# Sheet1.net
KiCad netlist of a schematic drawn in Altium Designer
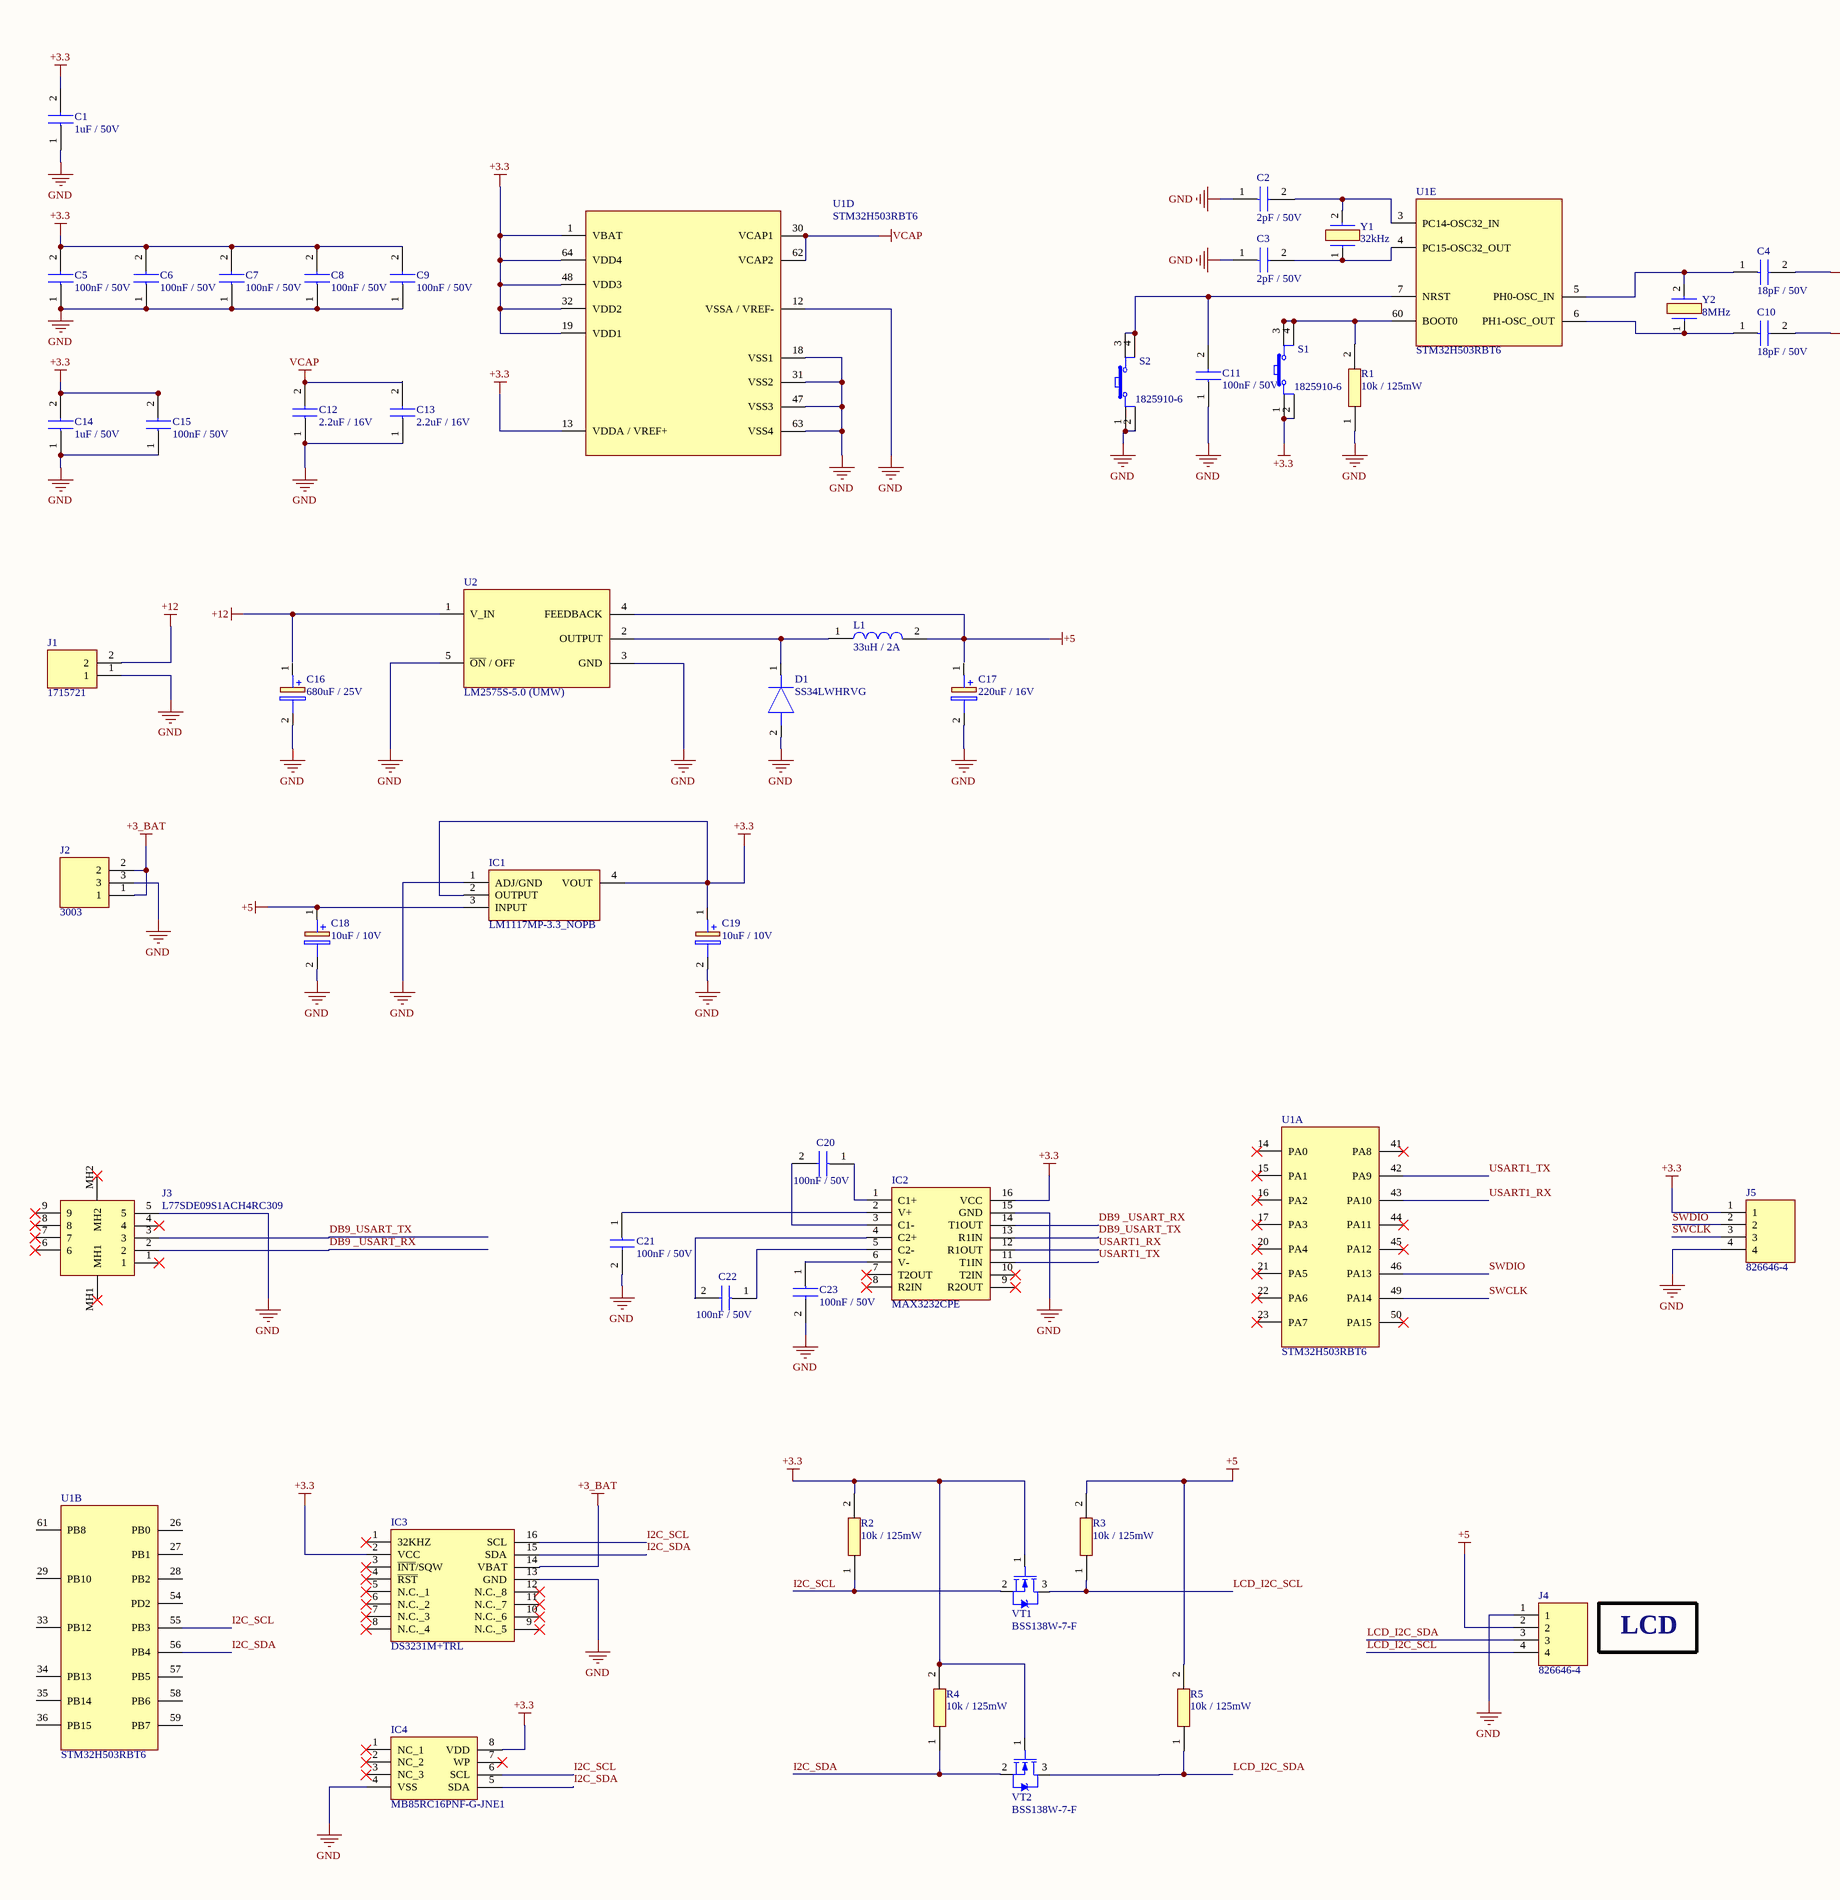
[diagram p0: Sheet1.SchDoc, left]
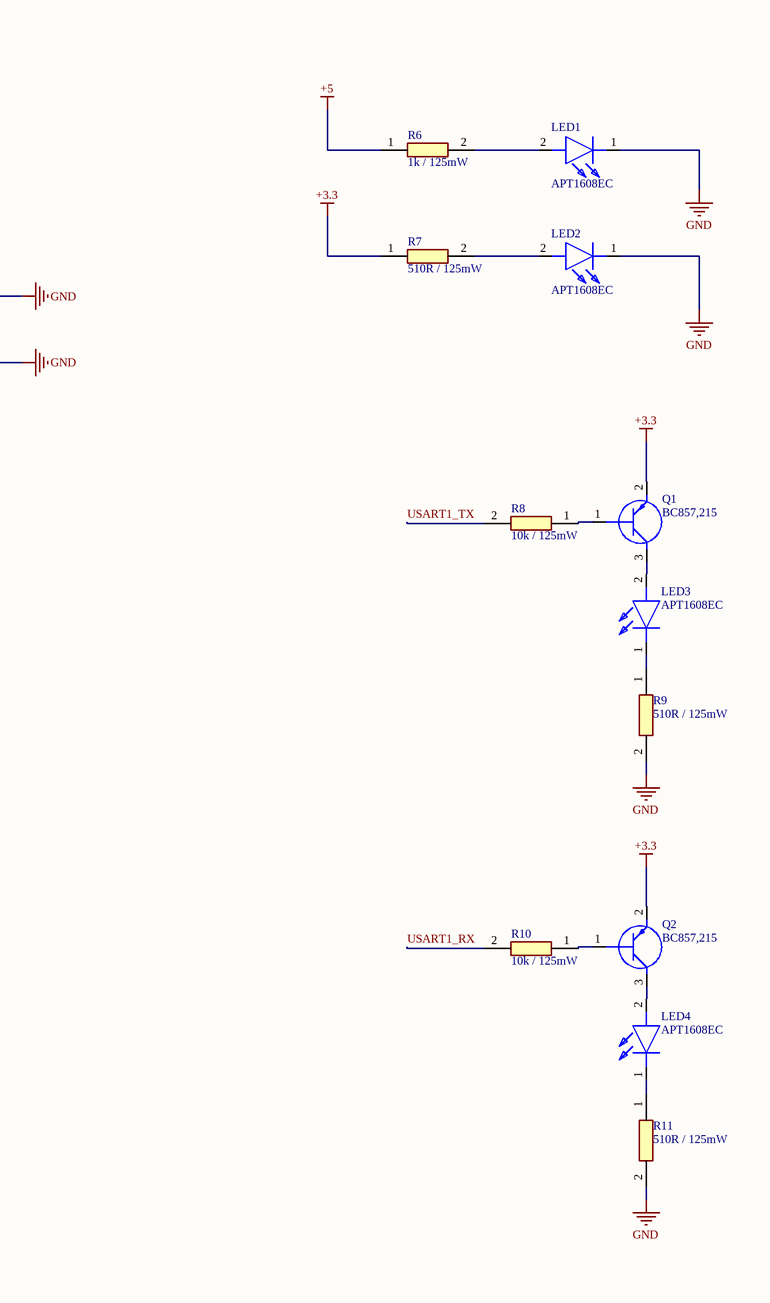
[diagram p1: Sheet1.SchDoc, right]

(export (version "E")
  (design (tool "Eeschema 10.0.6"))
  (components
    (comp (ref "C1")
      (value "1uF / 50V")
      (footprint "SamacSys:CAPC2012X145N")
      (description "Capacitor")
      (fields
        (field (name "MANUFACTURER_PART_NUMBER") "GRM21BR71H105KA12L")
        (field (name "MOUSER PART NUMBER") "81-GRM21BR71H105KA2L")
      )
      (libsource (lib "*") (part "GRM21BR71H105KA12L"))
    )
    (comp (ref "C2")
      (value "2pF / 50V")
      (footprint "SamacSys:C0805")
      (description "Capacitor")
      (fields (field (name "MANUFACTURER_PART_NUMBER") "C0805C209C5GACTU"))
      (libsource (lib "*") (part "C0805C209C5GACTU"))
    )
    (comp (ref "C3")
      (value "2pF / 50V")
      (footprint "SamacSys:C0805")
      (description "Capacitor")
      (fields (field (name "MANUFACTURER_PART_NUMBER") "C0805C209C5GACTU"))
      (libsource (lib "*") (part "C0805C209C5GACTU"))
    )
    (comp (ref "C4")
      (value "18pF / 50V")
      (footprint "SamacSys:C0805")
      (description "Capacitor")
      (fields
        (field (name "MANUFACTURER_PART_NUMBER") "C0805C180G5GACTU")
        (field (name "MOUSER PART NUMBER") "80-C0805C180G5G")
      )
      (libsource (lib "*") (part "C0805C180G5GACTU"))
    )
    (comp (ref "C5")
      (value "100nF / 50V")
      (footprint "SamacSys:CAPC2012X95N")
      (description "Capacitor")
      (fields
        (field (name "MANUFACTURER_PART_NUMBER") "CL21B104KBCNNNC")
        (field (name "MOUSER PART NUMBER") "187-CL21B104KBCNNNC")
      )
      (libsource (lib "*") (part "CL21B104KBCNNNC"))
    )
    (comp (ref "C6")
      (value "100nF / 50V")
      (footprint "SamacSys:CAPC2012X95N")
      (description "Capacitor")
      (fields
        (field (name "MANUFACTURER_PART_NUMBER") "CL21B104KBCNNNC")
        (field (name "MOUSER PART NUMBER") "187-CL21B104KBCNNNC")
      )
      (libsource (lib "*") (part "CL21B104KBCNNNC"))
    )
    (comp (ref "C7")
      (value "100nF / 50V")
      (footprint "SamacSys:CAPC2012X95N")
      (description "Capacitor")
      (fields
        (field (name "MANUFACTURER_PART_NUMBER") "CL21B104KBCNNNC")
        (field (name "MOUSER PART NUMBER") "187-CL21B104KBCNNNC")
      )
      (libsource (lib "*") (part "CL21B104KBCNNNC"))
    )
    (comp (ref "C8")
      (value "100nF / 50V")
      (footprint "SamacSys:CAPC2012X95N")
      (description "Capacitor")
      (fields
        (field (name "MANUFACTURER_PART_NUMBER") "CL21B104KBCNNNC")
        (field (name "MOUSER PART NUMBER") "187-CL21B104KBCNNNC")
      )
      (libsource (lib "*") (part "CL21B104KBCNNNC"))
    )
    (comp (ref "C9")
      (value "100nF / 50V")
      (footprint "SamacSys:CAPC2012X95N")
      (description "Capacitor")
      (fields
        (field (name "MANUFACTURER_PART_NUMBER") "CL21B104KBCNNNC")
        (field (name "MOUSER PART NUMBER") "187-CL21B104KBCNNNC")
      )
      (libsource (lib "*") (part "CL21B104KBCNNNC"))
    )
    (comp (ref "C10")
      (value "18pF / 50V")
      (footprint "SamacSys:C0805")
      (description "Capacitor")
      (fields
        (field (name "MANUFACTURER_PART_NUMBER") "C0805C180G5GACTU")
        (field (name "MOUSER PART NUMBER") "80-C0805C180G5G")
      )
      (libsource (lib "*") (part "C0805C180G5GACTU"))
    )
    (comp (ref "C11")
      (value "100nF / 50V")
      (footprint "SamacSys:CAPC2012X95N")
      (description "Capacitor")
      (fields
        (field (name "MANUFACTURER_PART_NUMBER") "CL21B104KBCNNNC")
        (field (name "MOUSER PART NUMBER") "187-CL21B104KBCNNNC")
      )
      (libsource (lib "*") (part "CL21B104KBCNNNC"))
    )
    (comp (ref "C12")
      (value "2.2uF / 16V")
      (footprint "SamacSys:CAPC2012X145N")
      (description "Capacitor")
      (fields
        (field (name "MANUFACTURER_PART_NUMBER") "GRM21BR71C225KA12L")
        (field (name "MOUSER PART NUMBER") "81-GRM21BR71C225KA2L")
      )
      (libsource (lib "*") (part "GRM21BR71C225KA12L"))
    )
    (comp (ref "C13")
      (value "2.2uF / 16V")
      (footprint "SamacSys:CAPC2012X145N")
      (description "Capacitor")
      (fields
        (field (name "MANUFACTURER_PART_NUMBER") "GRM21BR71C225KA12L")
        (field (name "MOUSER PART NUMBER") "81-GRM21BR71C225KA2L")
      )
      (libsource (lib "*") (part "GRM21BR71C225KA12L"))
    )
    (comp (ref "C14")
      (value "1uF / 50V")
      (footprint "SamacSys:CAPC2012X145N")
      (description "Capacitor")
      (fields
        (field (name "MANUFACTURER_PART_NUMBER") "GRM21BR71H105KA12L")
        (field (name "MOUSER PART NUMBER") "81-GRM21BR71H105KA2L")
      )
      (libsource (lib "*") (part "GRM21BR71H105KA12L"))
    )
    (comp (ref "C15")
      (value "100nF / 50V")
      (footprint "SamacSys:CAPC2012X95N")
      (description "Capacitor")
      (fields
        (field (name "MANUFACTURER_PART_NUMBER") "CL21B104KBCNNNC")
        (field (name "MOUSER PART NUMBER") "187-CL21B104KBCNNNC")
      )
      (libsource (lib "*") (part "CL21B104KBCNNNC"))
    )
    (comp (ref "C16")
      (value "680uF / 25V")
      (footprint "SamacSys:CAPPRD500W65D1000H1750")
      (description "Capacitor Polarised")
      (fields
        (field (name "MANUFACTURER_PART_NUMBER") "EEU-FP1E681B")
        (field (name "MOUSER PART NUMBER") "667-EEU-FP1E681B")
      )
      (libsource (lib "*") (part "EEU-FP1E681B"))
    )
    (comp (ref "C17")
      (value "220uF / 16V")
      (footprint "SamacSys:EEEFK0J331AL")
      (description "Capacitor Polarised")
      (fields (field (name "MANUFACTURER_PART_NUMBER") "EEE-FP1C221AL"))
      (libsource (lib "*") (part "EEE-FP1C221AL"))
    )
    (comp (ref "C18")
      (value "10uF / 10V")
      (footprint "SamacSys:T491A")
      (description "Capacitor Polarised")
      (fields
        (field (name "MANUFACTURER_PART_NUMBER") "T491A106K010AT")
        (field (name "MOUSER PART NUMBER") "80-T491A106K010")
      )
      (libsource (lib "*") (part "T491A106K010AT"))
    )
    (comp (ref "C19")
      (value "10uF / 10V")
      (footprint "SamacSys:T491A")
      (description "Capacitor Polarised")
      (fields
        (field (name "MANUFACTURER_PART_NUMBER") "T491A106K010AT")
        (field (name "MOUSER PART NUMBER") "80-T491A106K010")
      )
      (libsource (lib "*") (part "T491A106K010AT"))
    )
    (comp (ref "C20")
      (value "100nF / 50V")
      (footprint "SamacSys:CAPC2012X95N")
      (description "Capacitor")
      (fields
        (field (name "MANUFACTURER_PART_NUMBER") "CL21B104KBCNNNC")
        (field (name "MOUSER PART NUMBER") "187-CL21B104KBCNNNC")
      )
      (libsource (lib "*") (part "CL21B104KBCNNNC"))
    )
    (comp (ref "C21")
      (value "100nF / 50V")
      (footprint "SamacSys:CAPC2012X95N")
      (description "Capacitor")
      (fields
        (field (name "MANUFACTURER_PART_NUMBER") "CL21B104KBCNNNC")
        (field (name "MOUSER PART NUMBER") "187-CL21B104KBCNNNC")
      )
      (libsource (lib "*") (part "CL21B104KBCNNNC"))
    )
    (comp (ref "C22")
      (value "100nF / 50V")
      (footprint "SamacSys:CAPC2012X95N")
      (description "Capacitor")
      (fields
        (field (name "MANUFACTURER_PART_NUMBER") "CL21B104KBCNNNC")
        (field (name "MOUSER PART NUMBER") "187-CL21B104KBCNNNC")
      )
      (libsource (lib "*") (part "CL21B104KBCNNNC"))
    )
    (comp (ref "C23")
      (value "100nF / 50V")
      (footprint "SamacSys:CAPC2012X95N")
      (description "Capacitor")
      (fields
        (field (name "MANUFACTURER_PART_NUMBER") "CL21B104KBCNNNC")
        (field (name "MOUSER PART NUMBER") "187-CL21B104KBCNNNC")
      )
      (libsource (lib "*") (part "CL21B104KBCNNNC"))
    )
    (comp (ref "D1")
      (value "SS34LWHRVG")
      (footprint "SamacSys:SODFL3718X102N")
      (description "Diode")
      (fields (field (name "MOUSER PART NUMBER") "821-SS34LWHRVG"))
      (libsource (lib "*") (part "SS34LWHRVG"))
    )
    (comp (ref "D2") (value "LCD") (footprint "LCD") (libsource (lib "Library") (part "LCD")))
    (comp (ref "IC1")
      (value "LM1117MP-3.3_NOPB")
      (footprint "SamacSys:SOT230P700X180-4N")
      (description "Integrated Circuit")
      (fields
        (field (name "MANUFACTURER_PART_NUMBER") "LM1117MP-3.3/NOPB")
        (field (name "MOUSER PART NUMBER") "926-LM1117MP-3.3NOPB")
      )
      (libsource (lib "*") (part "LM1117MP-3.3_NOPB"))
    )
    (comp (ref "IC2")
      (value "MAX3232CPE")
      (footprint "SamacSys:DIP794W56P254L1918H457Q16N")
      (description "Integrated Circuit")
      (libsource (lib "*") (part "MAX3232CPE"))
    )
    (comp (ref "IC3")
      (value "DS3231M+TRL")
      (footprint "SamacSys:SOIC127P1032X265-16N")
      (description "Integrated Circuit")
      (fields (field (name "MOUSER PART NUMBER") "700-DS3231M+TRL"))
      (libsource (lib "*") (part "DS3231M+TRL"))
    )
    (comp (ref "IC4")
      (value "MB85RC16PNF-G-JNE1")
      (footprint "SamacSys:SOIC127P600X175-8N")
      (description "Integrated Circuit")
      (libsource (lib "*") (part "MB85RC16PNF-G-JNE1"))
    )
    (comp (ref "J1")
      (value "1715721")
      (footprint "SamacSys:1715721")
      (description "Connector")
      (fields (field (name "MOUSER PART NUMBER") "651-1715721"))
      (libsource (lib "*") (part "1715721"))
    )
    (comp (ref "J2")
      (value "3003")
      (footprint "SamacSys:3003")
      (description "Connector")
      (fields (field (name "MOUSER PART NUMBER") "534-3003"))
      (libsource (lib "*") (part "3003"))
    )
    (comp (ref "J3")
      (value "L77SDE09S1ACH4RC309")
      (footprint "SamacSys:L77SDE09S1ACH4RC309")
      (description "Connector")
      (fields (field (name "MOUSER PART NUMBER") "523-SDE09S1ACH4RC309"))
      (libsource (lib "*") (part "L77SDE09S1ACH4RC309"))
    )
    (comp (ref "J4")
      (value "826646-4")
      (footprint "SamacSys:HDRV4W68P0X254_1X4_1016X250X880P")
      (description "Connector")
      (fields (field (name "MOUSER PART NUMBER") "571-826646-4"))
      (libsource (lib "*") (part "826646-4"))
    )
    (comp (ref "J5")
      (value "826646-4")
      (footprint "SamacSys:HDRV4W68P0X254_1X4_1016X250X880P")
      (description "Connector")
      (fields (field (name "MOUSER PART NUMBER") "571-826646-4"))
      (libsource (lib "*") (part "826646-4"))
    )
    (comp (ref "L1")
      (value "33uH / 2A")
      (footprint "SamacSys:RLB0912330KL")
      (description "Inductor")
      (fields
        (field (name "MANUFACTURER_PART_NUMBER") "RLB0912-330KL")
        (field (name "MOUSER PART NUMBER") "652-RLB0912-330KL")
      )
      (libsource (lib "*") (part "RLB0912-330KL"))
    )
    (comp (ref "LED1")
      (value "APT1608EC")
      (footprint "SamacSys:LEDC1608X85N")
      (description "LED")
      (fields (field (name "MOUSER PART NUMBER") "604-APT1608EC"))
      (libsource (lib "*") (part "APT1608EC"))
    )
    (comp (ref "LED2")
      (value "APT1608EC")
      (footprint "SamacSys:LEDC1608X85N")
      (description "LED")
      (fields (field (name "MOUSER PART NUMBER") "604-APT1608EC"))
      (libsource (lib "*") (part "APT1608EC"))
    )
    (comp (ref "LED3")
      (value "APT1608EC")
      (footprint "SamacSys:LEDC1608X85N")
      (description "LED")
      (fields (field (name "MOUSER PART NUMBER") "604-APT1608EC"))
      (libsource (lib "*") (part "APT1608EC"))
    )
    (comp (ref "LED4")
      (value "APT1608EC")
      (footprint "SamacSys:LEDC1608X85N")
      (description "LED")
      (fields (field (name "MOUSER PART NUMBER") "604-APT1608EC"))
      (libsource (lib "*") (part "APT1608EC"))
    )
    (comp (ref "Q1")
      (value "BC857,215")
      (footprint "SamacSys:BC857215")
      (description "Transistor BJT PNP")
      (fields (field (name "MOUSER PART NUMBER") "771-BC857215"))
      (libsource (lib "*") (part "BC857,215"))
    )
    (comp (ref "Q2")
      (value "BC857,215")
      (footprint "SamacSys:BC857215")
      (description "Transistor BJT PNP")
      (fields (field (name "MOUSER PART NUMBER") "771-BC857215"))
      (libsource (lib "*") (part "BC857,215"))
    )
    (comp (ref "R1")
      (value "10k / 125mW")
      (footprint "SamacSys:RESC2012X60N")
      (description "Resistor")
      (fields
        (field (name "MANUFACTURER_PART_NUMBER") "RC0805FR-0710KL")
        (field (name "MOUSER PART NUMBER") "603-RC0805FR-0710KL")
      )
      (libsource (lib "") (part "RC0805FR-0710KL_1"))
    )
    (comp (ref "R2")
      (value "10k / 125mW")
      (footprint "SamacSys:RESC2012X60N")
      (description "Resistor")
      (fields
        (field (name "MANUFACTURER_PART_NUMBER") "RC0805FR-0710KL")
        (field (name "MOUSER PART NUMBER") "603-RC0805FR-0710KL")
      )
      (libsource (lib "") (part "RC0805FR-0710KL_1"))
    )
    (comp (ref "R3")
      (value "10k / 125mW")
      (footprint "SamacSys:RESC2012X60N")
      (description "Resistor")
      (fields
        (field (name "MANUFACTURER_PART_NUMBER") "RC0805FR-0710KL")
        (field (name "MOUSER PART NUMBER") "603-RC0805FR-0710KL")
      )
      (libsource (lib "") (part "RC0805FR-0710KL_1"))
    )
    (comp (ref "R4")
      (value "10k / 125mW")
      (footprint "SamacSys:RESC2012X60N")
      (description "Resistor")
      (fields
        (field (name "MANUFACTURER_PART_NUMBER") "RC0805FR-0710KL")
        (field (name "MOUSER PART NUMBER") "603-RC0805FR-0710KL")
      )
      (libsource (lib "") (part "RC0805FR-0710KL_1"))
    )
    (comp (ref "R5")
      (value "10k / 125mW")
      (footprint "SamacSys:RESC2012X60N")
      (description "Resistor")
      (fields
        (field (name "MANUFACTURER_PART_NUMBER") "RC0805FR-0710KL")
        (field (name "MOUSER PART NUMBER") "603-RC0805FR-0710KL")
      )
      (libsource (lib "") (part "RC0805FR-0710KL_1"))
    )
    (comp (ref "R6")
      (value "1k / 125mW")
      (footprint "SamacSys:RESC2013X65N")
      (description "Resistor")
      (fields
        (field (name "MANUFACTURER_PART_NUMBER") "0805W8F1001T5E")
        (field (name "MOUSER PART NUMBER") "303-0805W8F1001T5E")
      )
      (libsource (lib "*") (part "0805W8F1001T5E"))
    )
    (comp (ref "R7")
      (value "510R / 125mW")
      (footprint "SamacSys:ERJ6ENF1000V")
      (description "Resistor")
      (fields
        (field (name "MANUFACTURER_PART_NUMBER") "ERJ-6ENF5100V")
        (field (name "MOUSER PART NUMBER") "667-ERJ-6ENF5100V")
      )
      (libsource (lib "*") (part "ERJ-6ENF5100V"))
    )
    (comp (ref "R8")
      (value "10k / 125mW")
      (footprint "SamacSys:RESC2012X60N")
      (description "Resistor")
      (fields
        (field (name "MANUFACTURER_PART_NUMBER") "RC0805FR-0710KL")
        (field (name "MOUSER PART NUMBER") "603-RC0805FR-0710KL")
      )
      (libsource (lib "*") (part "RC0805FR-0710KL"))
    )
    (comp (ref "R9")
      (value "510R / 125mW")
      (footprint "SamacSys:ERJ6ENF1000V")
      (description "Resistor")
      (fields
        (field (name "MANUFACTURER_PART_NUMBER") "ERJ-6ENF5100V")
        (field (name "MOUSER PART NUMBER") "667-ERJ-6ENF5100V")
      )
      (libsource (lib "") (part "ERJ-6ENF5100V_1"))
    )
    (comp (ref "R10")
      (value "10k / 125mW")
      (footprint "SamacSys:RESC2012X60N")
      (description "Resistor")
      (fields
        (field (name "MANUFACTURER_PART_NUMBER") "RC0805FR-0710KL")
        (field (name "MOUSER PART NUMBER") "603-RC0805FR-0710KL")
      )
      (libsource (lib "*") (part "RC0805FR-0710KL"))
    )
    (comp (ref "R11")
      (value "510R / 125mW")
      (footprint "SamacSys:ERJ6ENF1000V")
      (description "Resistor")
      (fields
        (field (name "MANUFACTURER_PART_NUMBER") "ERJ-6ENF5100V")
        (field (name "MOUSER PART NUMBER") "667-ERJ-6ENF5100V")
      )
      (libsource (lib "") (part "ERJ-6ENF5100V_1"))
    )
    (comp (ref "S1")
      (value "1825910-6")
      (footprint "TE_1825910-6")
      (description "Switch Tactile OFF (ON) SPST Round Button PC Pins 0.05A 24VDC 1.57N Thru-Hole Loose")
      (fields (field (name "MANUFACTURER") "TE Connectivity"))
      (libsource (lib "Library") (part "1825910-6"))
    )
    (comp (ref "S2")
      (value "1825910-6")
      (footprint "TE_1825910-6")
      (description "Switch Tactile OFF (ON) SPST Round Button PC Pins 0.05A 24VDC 1.57N Thru-Hole Loose")
      (fields (field (name "MANUFACTURER") "TE Connectivity"))
      (libsource (lib "Library") (part "1825910-6"))
    )
    (comp (ref "U1")
      (value "STM32H503RBT6")
      (footprint "QFP64P50_1200X1200X160L60X22N")
      (description "RISC Microcontroller, 32-Bit, FLASH, CORTEX-M4F CPU, 180MHz, CMOS, PBGA216")
      (fields (field (name "MANUFACTURER") "STMicroelectronics"))
      (libsource (lib "") (part "STM32H503RBT6_2"))
    )
    (comp (ref "U2")
      (value "LM2575S-5.0 (UMW)")
      (footprint "DPAK6P170_1534X467L254X81T736X1018N")
      (description "52kHz Buck Fixed 2A 5V TO-263-5 Voltage Regulators - DC DC Switching Regulators RoHS")
      (fields
        (field (name "MANUFACTURER") "UMW")
        (field (name "MANUFACTURER PART NUMBER") "LM2575S-5.0(UMW)")
      )
      (libsource (lib "Library") (part "LM2575S-5.0 (UMW)"))
    )
    (comp (ref "VT1")
      (value "BSS138W-7-F")
      (footprint "SOT23-3P65_222X100L35X30N")
      (description "Transistor: N-MOSFET; unipolar; 50V; 0.2A; 3.5ohm; 0.2W; -55+150 deg.C; SMD; SOT323(SC70)")
      (fields (field (name "MANUFACTURER") "Diodes Inc.") (field (name "VOLTAGE") "50V"))
      (libsource (lib "Library") (part "BSS138W-7-F"))
    )
    (comp (ref "VT2")
      (value "BSS138W-7-F")
      (footprint "SOT23-3P65_222X100L35X30N")
      (description "Transistor: N-MOSFET; unipolar; 50V; 0.2A; 3.5ohm; 0.2W; -55+150 deg.C; SMD; SOT323(SC70)")
      (fields (field (name "MANUFACTURER") "Diodes Inc.") (field (name "VOLTAGE") "50V"))
      (libsource (lib "Library") (part "BSS138W-7-F"))
    )
    (comp (ref "Y1")
      (value "32kHz")
      (footprint "SamacSys:ABS06")
      (description "Crystal or Oscillator")
      (fields
        (field (name "MANUFACTURER_PART_NUMBER") "ABS06-107-32.768KHZ-T")
        (field (name "MOUSER PART NUMBER") "815-ABS06-107-32.7-T")
      )
      (libsource (lib "*") (part "ABS06-107-32.768KHZ-T"))
    )
    (comp (ref "Y2")
      (value "8MHz")
      (footprint "SamacSys:ABLS8000MHz12B4YT")
      (description "Crystal or Oscillator")
      (fields
        (field (name "MANUFACTURER_PART_NUMBER") "ABLS-8.000MHZ-12-B-4-Y-T")
        (field (name "MOUSER PART NUMBER") "815-LS8000MHZ12B4YT")
      )
      (libsource (lib "*") (part "ABLS-8.000MHZ-12-B-4-Y-T"))
    )
  )
  (nets
    (net (code "1") (name "+3.3") (class "Default")
      (node (ref "C1") (pin "2") (pinfunction "2_2") (pintype "passive"))
      (node (ref "C14") (pin "2") (pinfunction "2_2") (pintype "passive"))
      (node (ref "C15") (pin "2") (pinfunction "2_2") (pintype "passive"))
      (node (ref "C19") (pin "1") (pinfunction "+_1") (pintype "passive"))
      (node (ref "C5") (pin "2") (pinfunction "2_2") (pintype "passive"))
      (node (ref "C6") (pin "2") (pinfunction "2_2") (pintype "passive"))
      (node (ref "C7") (pin "2") (pinfunction "2_2") (pintype "passive"))
      (node (ref "C8") (pin "2") (pinfunction "2_2") (pintype "passive"))
      (node (ref "C9") (pin "2") (pinfunction "2_2") (pintype "passive"))
      (node (ref "IC1") (pin "2") (pinfunction "OUTPUT_2") (pintype "passive"))
      (node (ref "IC1") (pin "4") (pinfunction "VOUT_4") (pintype "passive"))
      (node (ref "IC2") (pin "16") (pinfunction "VCC_16") (pintype "passive"))
      (node (ref "IC3") (pin "2") (pinfunction "VCC_2") (pintype "passive"))
      (node (ref "IC4") (pin "8") (pinfunction "VDD_8") (pintype "passive"))
      (node (ref "J5") (pin "1") (pinfunction "1_1") (pintype "passive"))
      (node (ref "Q1") (pin "2") (pinfunction "E_2") (pintype "passive"))
      (node (ref "Q2") (pin "2") (pinfunction "E_2") (pintype "passive"))
      (node (ref "R2") (pin "2") (pinfunction "2_2") (pintype "passive"))
      (node (ref "R4") (pin "2") (pinfunction "2_2") (pintype "passive"))
      (node (ref "R7") (pin "1") (pinfunction "1_1") (pintype "passive"))
      (node (ref "S1") (pin "1") (pinfunction "1_1") (pintype "passive"))
      (node (ref "S1") (pin "2") (pinfunction "2_2") (pintype "passive"))
      (node (ref "U1") (pin "1") (pinfunction "VBAT_1") (pintype "passive"))
      (node (ref "U1") (pin "13") (pinfunction "VDDA_/_VREF+_13") (pintype "passive"))
      (node (ref "U1") (pin "19") (pinfunction "VDD1_19") (pintype "passive"))
      (node (ref "U1") (pin "32") (pinfunction "VDD2_32") (pintype "passive"))
      (node (ref "U1") (pin "48") (pinfunction "VDD3_48") (pintype "passive"))
      (node (ref "U1") (pin "64") (pinfunction "VDD4_64") (pintype "passive"))
      (node (ref "VT1") (pin "1") (pinfunction "G_1") (pintype "passive"))
      (node (ref "VT2") (pin "1") (pinfunction "G_1") (pintype "passive"))
    )
    (net (code "2") (name "+3_BAT") (class "Default")
      (node (ref "IC3") (pin "14") (pinfunction "VBAT_14") (pintype "passive"))
      (node (ref "J2") (pin "1") (pinfunction "1_1") (pintype "passive"))
      (node (ref "J2") (pin "2") (pinfunction "2_2") (pintype "passive"))
    )
    (net (code "3") (name "+5") (class "Default")
      (node (ref "C18") (pin "1") (pinfunction "+_1") (pintype "passive"))
      (node (ref "IC1") (pin "3") (pinfunction "INPUT_3") (pintype "passive"))
      (node (ref "J4") (pin "2") (pinfunction "2_2") (pintype "passive"))
      (node (ref "L1") (pin "2") (pinfunction "2_2") (pintype "passive"))
      (node (ref "R3") (pin "2") (pinfunction "2_2") (pintype "passive"))
      (node (ref "R5") (pin "2") (pinfunction "2_2") (pintype "passive"))
      (node (ref "R6") (pin "1") (pinfunction "1_1") (pintype "passive"))
      (node (ref "U2") (pin "4") (pinfunction "FEEDBACK_4") (pintype "passive"))
    )
    (net (code "4") (name "+12") (class "Default")
      (node (ref "J1") (pin "2") (pinfunction "2_2") (pintype "passive"))
      (node (ref "U2") (pin "1") (pinfunction "V_IN_1") (pintype "passive"))
    )
    (net (code "5") (name "/DB9 _USART_RX") (class "Default")
      (node (ref "IC2") (pin "14") (pinfunction "T1OUT_14") (pintype "passive"))
      (node (ref "J3") (pin "2") (pinfunction "2_2") (pintype "passive"))
    )
    (net (code "6") (name "/DB9_USART_TX") (class "Default")
      (node (ref "IC2") (pin "13") (pinfunction "R1IN_13") (pintype "passive"))
      (node (ref "J3") (pin "3") (pinfunction "3_3") (pintype "passive"))
    )
    (net (code "7") (name "/I2C_SCL") (class "Default")
      (node (ref "IC3") (pin "16") (pinfunction "SCL_16") (pintype "passive"))
      (node (ref "IC4") (pin "6") (pinfunction "SCL_6") (pintype "passive"))
      (node (ref "R2") (pin "1") (pinfunction "1_1") (pintype "passive"))
      (node (ref "U1") (pin "55") (pinfunction "PB3_55") (pintype "passive"))
    )
    (net (code "8") (name "/I2C_SDA") (class "Default")
      (node (ref "IC3") (pin "15") (pinfunction "SDA_15") (pintype "passive"))
      (node (ref "IC4") (pin "5") (pinfunction "SDA_5") (pintype "passive"))
      (node (ref "R4") (pin "1") (pinfunction "1_1") (pintype "passive"))
      (node (ref "U1") (pin "56") (pinfunction "PB4_56") (pintype "passive"))
      (node (ref "VT2") (pin "2") (pinfunction "S_2") (pintype "passive"))
    )
    (net (code "9") (name "/LCD_I2C_SCL") (class "Default")
      (node (ref "J4") (pin "4") (pinfunction "4_4") (pintype "passive"))
      (node (ref "R3") (pin "1") (pinfunction "1_1") (pintype "passive"))
    )
    (net (code "10") (name "/LCD_I2C_SDA") (class "Default")
      (node (ref "J4") (pin "3") (pinfunction "3_3") (pintype "passive"))
      (node (ref "R5") (pin "1") (pinfunction "1_1") (pintype "passive"))
      (node (ref "VT2") (pin "3") (pinfunction "D_3") (pintype "passive"))
    )
    (net (code "11") (name "/SWCLK") (class "Default")
      (node (ref "J5") (pin "3") (pinfunction "3_3") (pintype "passive"))
      (node (ref "U1") (pin "49") (pinfunction "PA14_49") (pintype "passive"))
    )
    (net (code "12") (name "/SWDIO") (class "Default")
      (node (ref "J5") (pin "2") (pinfunction "2_2") (pintype "passive"))
      (node (ref "U1") (pin "46") (pinfunction "PA13_46") (pintype "passive"))
    )
    (net (code "13") (name "/USART1_RX") (class "Default")
      (node (ref "IC2") (pin "12") (pinfunction "R1OUT_12") (pintype "passive"))
      (node (ref "R10") (pin "2") (pinfunction "2_2") (pintype "passive"))
      (node (ref "U1") (pin "43") (pinfunction "PA10_43") (pintype "passive"))
    )
    (net (code "14") (name "/USART1_TX") (class "Default")
      (node (ref "IC2") (pin "11") (pinfunction "T1IN_11") (pintype "passive"))
      (node (ref "R8") (pin "2") (pinfunction "2_2") (pintype "passive"))
      (node (ref "U1") (pin "42") (pinfunction "PA9_42") (pintype "passive"))
    )
    (net (code "15") (name "GND") (class "Default")
      (node (ref "C1") (pin "1") (pinfunction "1_1") (pintype "passive"))
      (node (ref "C10") (pin "2") (pinfunction "2_2") (pintype "passive"))
      (node (ref "C11") (pin "1") (pinfunction "1_1") (pintype "passive"))
      (node (ref "C12") (pin "1") (pinfunction "1_1") (pintype "passive"))
      (node (ref "C13") (pin "1") (pinfunction "1_1") (pintype "passive"))
      (node (ref "C14") (pin "1") (pinfunction "1_1") (pintype "passive"))
      (node (ref "C15") (pin "1") (pinfunction "1_1") (pintype "passive"))
      (node (ref "C16") (pin "2") (pinfunction "-_2") (pintype "passive"))
      (node (ref "C17") (pin "2") (pinfunction "-_2") (pintype "passive"))
      (node (ref "C18") (pin "2") (pinfunction "-_2") (pintype "passive"))
      (node (ref "C19") (pin "2") (pinfunction "-_2") (pintype "passive"))
      (node (ref "C2") (pin "1") (pinfunction "1_1") (pintype "passive"))
      (node (ref "C21") (pin "2") (pinfunction "2_2") (pintype "passive"))
      (node (ref "C23") (pin "2") (pinfunction "2_2") (pintype "passive"))
      (node (ref "C3") (pin "1") (pinfunction "1_1") (pintype "passive"))
      (node (ref "C4") (pin "2") (pinfunction "2_2") (pintype "passive"))
      (node (ref "C5") (pin "1") (pinfunction "1_1") (pintype "passive"))
      (node (ref "C6") (pin "1") (pinfunction "1_1") (pintype "passive"))
      (node (ref "C7") (pin "1") (pinfunction "1_1") (pintype "passive"))
      (node (ref "C8") (pin "1") (pinfunction "1_1") (pintype "passive"))
      (node (ref "C9") (pin "1") (pinfunction "1_1") (pintype "passive"))
      (node (ref "D1") (pin "2") (pinfunction "A_2") (pintype "passive"))
      (node (ref "IC1") (pin "1") (pinfunction "ADJ/GND_1") (pintype "passive"))
      (node (ref "IC2") (pin "15") (pinfunction "GND_15") (pintype "passive"))
      (node (ref "IC3") (pin "13") (pinfunction "GND_13") (pintype "passive"))
      (node (ref "IC4") (pin "4") (pinfunction "VSS_4") (pintype "passive"))
      (node (ref "J1") (pin "1") (pinfunction "1_1") (pintype "passive"))
      (node (ref "J2") (pin "3") (pinfunction "3_3") (pintype "passive"))
      (node (ref "J3") (pin "5") (pinfunction "5_5") (pintype "passive"))
      (node (ref "J4") (pin "1") (pinfunction "1_1") (pintype "passive"))
      (node (ref "J5") (pin "4") (pinfunction "4_4") (pintype "passive"))
      (node (ref "LED1") (pin "1") (pinfunction "K_1") (pintype "passive"))
      (node (ref "LED2") (pin "1") (pinfunction "K_1") (pintype "passive"))
      (node (ref "R1") (pin "1") (pinfunction "1_1") (pintype "passive"))
      (node (ref "R11") (pin "2") (pinfunction "2_2") (pintype "passive"))
      (node (ref "R9") (pin "2") (pinfunction "2_2") (pintype "passive"))
      (node (ref "S2") (pin "1") (pinfunction "1_1") (pintype "passive"))
      (node (ref "S2") (pin "2") (pinfunction "2_2") (pintype "passive"))
      (node (ref "U1") (pin "12") (pinfunction "VSSA_/_VREF-_12") (pintype "passive"))
      (node (ref "U1") (pin "18") (pinfunction "VSS1_18") (pintype "passive"))
      (node (ref "U1") (pin "31") (pinfunction "VSS2_31") (pintype "passive"))
      (node (ref "U1") (pin "47") (pinfunction "VSS3_47") (pintype "passive"))
      (node (ref "U1") (pin "63") (pinfunction "VSS4_63") (pintype "passive"))
      (node (ref "U2") (pin "3") (pinfunction "GND_3") (pintype "passive"))
      (node (ref "U2") (pin "5") (pinfunction "~{ON}_/_OFF_5") (pintype "passive"))
    )
    (net (code "16") (name "Net-(D1-K)") (class "Default")
      (node (ref "D1") (pin "1") (pinfunction "K_1") (pintype "passive"))
      (node (ref "L1") (pin "1") (pinfunction "1_1") (pintype "passive"))
      (node (ref "U2") (pin "2") (pinfunction "OUTPUT_2") (pintype "passive"))
    )
    (net (code "17") (name "Net-(IC2-C1+)") (class "Default")
      (node (ref "C20") (pin "1") (pinfunction "1_1") (pintype "passive"))
      (node (ref "IC2") (pin "1") (pinfunction "C1+_1") (pintype "passive"))
    )
    (net (code "18") (name "Net-(IC2-C1-)") (class "Default")
      (node (ref "C20") (pin "2") (pinfunction "2_2") (pintype "passive"))
      (node (ref "IC2") (pin "3") (pinfunction "C1-_3") (pintype "passive"))
    )
    (net (code "19") (name "Net-(IC2-C2+)") (class "Default")
      (node (ref "C22") (pin "2") (pinfunction "2_2") (pintype "passive"))
      (node (ref "IC2") (pin "4") (pinfunction "C2+_4") (pintype "passive"))
    )
    (net (code "20") (name "Net-(IC2-C2-)") (class "Default")
      (node (ref "C22") (pin "1") (pinfunction "1_1") (pintype "passive"))
      (node (ref "IC2") (pin "5") (pinfunction "C2-_5") (pintype "passive"))
    )
    (net (code "21") (name "Net-(IC2-V+)") (class "Default")
      (node (ref "C21") (pin "1") (pinfunction "1_1") (pintype "passive"))
      (node (ref "IC2") (pin "2") (pinfunction "V+_2") (pintype "passive"))
    )
    (net (code "22") (name "Net-(IC2-V-)") (class "Default")
      (node (ref "C23") (pin "1") (pinfunction "1_1") (pintype "passive"))
      (node (ref "IC2") (pin "6") (pinfunction "V-_6") (pintype "passive"))
    )
    (net (code "23") (name "Net-(LED1-A)") (class "Default")
      (node (ref "LED1") (pin "2") (pinfunction "A_2") (pintype "passive"))
      (node (ref "R6") (pin "2") (pinfunction "2_2") (pintype "passive"))
    )
    (net (code "24") (name "Net-(LED2-A)") (class "Default")
      (node (ref "LED2") (pin "2") (pinfunction "A_2") (pintype "passive"))
      (node (ref "R7") (pin "2") (pinfunction "2_2") (pintype "passive"))
    )
    (net (code "25") (name "Net-(LED3-A)") (class "Default")
      (node (ref "LED3") (pin "2") (pinfunction "A_2") (pintype "passive"))
      (node (ref "Q1") (pin "3") (pinfunction "C_3") (pintype "passive"))
    )
    (net (code "26") (name "Net-(LED3-K)") (class "Default")
      (node (ref "LED3") (pin "1") (pinfunction "K_1") (pintype "passive"))
      (node (ref "R9") (pin "1") (pinfunction "1_1") (pintype "passive"))
    )
    (net (code "27") (name "Net-(LED4-A)") (class "Default")
      (node (ref "LED4") (pin "2") (pinfunction "A_2") (pintype "passive"))
      (node (ref "Q2") (pin "3") (pinfunction "C_3") (pintype "passive"))
    )
    (net (code "28") (name "Net-(LED4-K)") (class "Default")
      (node (ref "LED4") (pin "1") (pinfunction "K_1") (pintype "passive"))
      (node (ref "R11") (pin "1") (pinfunction "1_1") (pintype "passive"))
    )
    (net (code "29") (name "Net-(Q1-B)") (class "Default")
      (node (ref "Q1") (pin "1") (pinfunction "B_1") (pintype "passive"))
      (node (ref "R8") (pin "1") (pinfunction "1_1") (pintype "passive"))
    )
    (net (code "30") (name "Net-(Q2-B)") (class "Default")
      (node (ref "Q2") (pin "1") (pinfunction "B_1") (pintype "passive"))
      (node (ref "R10") (pin "1") (pinfunction "1_1") (pintype "passive"))
    )
    (net (code "31") (name "Net-(U1E-BOOT0)") (class "Default")
      (node (ref "R1") (pin "2") (pinfunction "2_2") (pintype "passive"))
      (node (ref "S1") (pin "3") (pinfunction "3_3") (pintype "passive"))
      (node (ref "S1") (pin "4") (pinfunction "4_4") (pintype "passive"))
      (node (ref "U1") (pin "60") (pinfunction "BOOT0_60") (pintype "passive"))
    )
    (net (code "32") (name "Net-(U1E-NRST)") (class "Default")
      (node (ref "C11") (pin "2") (pinfunction "2_2") (pintype "passive"))
      (node (ref "S2") (pin "3") (pinfunction "3_3") (pintype "passive"))
      (node (ref "S2") (pin "4") (pinfunction "4_4") (pintype "passive"))
      (node (ref "U1") (pin "7") (pinfunction "NRST_7") (pintype "passive"))
    )
    (net (code "33") (name "Net-(U1E-PC14-OSC32_IN)") (class "Default")
      (node (ref "C2") (pin "2") (pinfunction "2_2") (pintype "passive"))
      (node (ref "U1") (pin "3") (pinfunction "PC14-OSC32_IN_3") (pintype "passive"))
      (node (ref "Y1") (pin "2") (pinfunction "2_2") (pintype "passive"))
    )
    (net (code "34") (name "Net-(U1E-PC15-OSC32_OUT)") (class "Default")
      (node (ref "C3") (pin "2") (pinfunction "2_2") (pintype "passive"))
      (node (ref "U1") (pin "4") (pinfunction "PC15-OSC32_OUT_4") (pintype "passive"))
      (node (ref "Y1") (pin "1") (pinfunction "1_1") (pintype "passive"))
    )
    (net (code "35") (name "Net-(U1E-PH0-OSC_IN)") (class "Default")
      (node (ref "C4") (pin "1") (pinfunction "1_1") (pintype "passive"))
      (node (ref "U1") (pin "5") (pinfunction "PH0-OSC_IN_5") (pintype "passive"))
      (node (ref "Y2") (pin "2") (pinfunction "2_2") (pintype "passive"))
    )
    (net (code "36") (name "Net-(U1E-PH1-OSC_OUT)") (class "Default")
      (node (ref "C10") (pin "1") (pinfunction "1_1") (pintype "passive"))
      (node (ref "U1") (pin "6") (pinfunction "PH1-OSC_OUT_6") (pintype "passive"))
      (node (ref "Y2") (pin "1") (pinfunction "1_1") (pintype "passive"))
    )
    (net (code "37") (name "VCAP") (class "Default")
      (node (ref "C12") (pin "2") (pinfunction "2_2") (pintype "passive"))
      (node (ref "U1") (pin "30") (pinfunction "VCAP1_30") (pintype "passive"))
      (node (ref "U1") (pin "62") (pinfunction "VCAP2_62") (pintype "passive"))
    )
    (net (code "38") (name "unconnected-(C13-Pad2)") (class "Default")
      (node (ref "C13") (pin "2") (pinfunction "2_2") (pintype "passive"))
    )
    (net (code "39") (name "unconnected-(C16-+-Pad1)") (class "Default")
      (node (ref "C16") (pin "1") (pinfunction "+_1") (pintype "passive"))
    )
    (net (code "40") (name "unconnected-(C17-+-Pad1)") (class "Default")
      (node (ref "C17") (pin "1") (pinfunction "+_1") (pintype "passive"))
    )
    (net (code "41") (name "unconnected-(IC2-R2IN-Pad8)") (class "Default")
      (node (ref "IC2") (pin "8") (pinfunction "R2IN_8") (pintype "passive+no_connect"))
    )
    (net (code "42") (name "unconnected-(IC2-R2OUT-Pad9)") (class "Default")
      (node (ref "IC2") (pin "9") (pinfunction "R2OUT_9") (pintype "passive+no_connect"))
    )
    (net (code "43") (name "unconnected-(IC2-T2IN-Pad10)") (class "Default")
      (node (ref "IC2") (pin "10") (pinfunction "T2IN_10") (pintype "passive+no_connect"))
    )
    (net (code "44") (name "unconnected-(IC2-T2OUT-Pad7)") (class "Default")
      (node (ref "IC2") (pin "7") (pinfunction "T2OUT_7") (pintype "passive+no_connect"))
    )
    (net (code "45") (name "unconnected-(IC3-32KHZ-Pad1)") (class "Default")
      (node (ref "IC3") (pin "1") (pinfunction "32KHZ_1") (pintype "passive+no_connect"))
    )
    (net (code "46") (name "unconnected-(IC3-N.C._1-Pad5)") (class "Default")
      (node (ref "IC3") (pin "5") (pinfunction "N.C._1_5") (pintype "passive+no_connect"))
    )
    (net (code "47") (name "unconnected-(IC3-N.C._2-Pad6)") (class "Default")
      (node (ref "IC3") (pin "6") (pinfunction "N.C._2_6") (pintype "passive+no_connect"))
    )
    (net (code "48") (name "unconnected-(IC3-N.C._3-Pad7)") (class "Default")
      (node (ref "IC3") (pin "7") (pinfunction "N.C._3_7") (pintype "passive+no_connect"))
    )
    (net (code "49") (name "unconnected-(IC3-N.C._4-Pad8)") (class "Default")
      (node (ref "IC3") (pin "8") (pinfunction "N.C._4_8") (pintype "passive+no_connect"))
    )
    (net (code "50") (name "unconnected-(IC3-N.C._5-Pad9)") (class "Default")
      (node (ref "IC3") (pin "9") (pinfunction "N.C._5_9") (pintype "passive+no_connect"))
    )
    (net (code "51") (name "unconnected-(IC3-N.C._6-Pad10)") (class "Default")
      (node (ref "IC3") (pin "10") (pinfunction "N.C._6_10") (pintype "passive+no_connect"))
    )
    (net (code "52") (name "unconnected-(IC3-N.C._7-Pad11)") (class "Default")
      (node (ref "IC3") (pin "11") (pinfunction "N.C._7_11") (pintype "passive+no_connect"))
    )
    (net (code "53") (name "unconnected-(IC3-N.C._8-Pad12)") (class "Default")
      (node (ref "IC3") (pin "12") (pinfunction "N.C._8_12") (pintype "passive+no_connect"))
    )
    (net (code "54") (name "unconnected-(IC3-~{INT}{slash}SQW-Pad3)") (class "Default")
      (node (ref "IC3") (pin "3") (pinfunction "~{INT}/SQW_3") (pintype "passive+no_connect"))
    )
    (net (code "55") (name "unconnected-(IC3-~{RST}-Pad4)") (class "Default")
      (node (ref "IC3") (pin "4") (pinfunction "~{RST}_4") (pintype "passive+no_connect"))
    )
    (net (code "56") (name "unconnected-(IC4-NC_1-Pad1)") (class "Default")
      (node (ref "IC4") (pin "1") (pinfunction "NC_1_1") (pintype "passive+no_connect"))
    )
    (net (code "57") (name "unconnected-(IC4-NC_2-Pad2)") (class "Default")
      (node (ref "IC4") (pin "2") (pinfunction "NC_2_2") (pintype "passive+no_connect"))
    )
    (net (code "58") (name "unconnected-(IC4-NC_3-Pad3)") (class "Default")
      (node (ref "IC4") (pin "3") (pinfunction "NC_3_3") (pintype "passive+no_connect"))
    )
    (net (code "59") (name "unconnected-(IC4-WP-Pad7)") (class "Default")
      (node (ref "IC4") (pin "7") (pinfunction "WP_7") (pintype "passive+no_connect"))
    )
    (net (code "60") (name "unconnected-(J3-Pad1)") (class "Default")
      (node (ref "J3") (pin "1") (pinfunction "1_1") (pintype "passive+no_connect"))
    )
    (net (code "61") (name "unconnected-(J3-Pad4)") (class "Default")
      (node (ref "J3") (pin "4") (pinfunction "4_4") (pintype "passive+no_connect"))
    )
    (net (code "62") (name "unconnected-(J3-Pad6)") (class "Default")
      (node (ref "J3") (pin "6") (pinfunction "6_6") (pintype "passive+no_connect"))
    )
    (net (code "63") (name "unconnected-(J3-Pad7)") (class "Default")
      (node (ref "J3") (pin "7") (pinfunction "7_7") (pintype "passive+no_connect"))
    )
    (net (code "64") (name "unconnected-(J3-Pad8)") (class "Default")
      (node (ref "J3") (pin "8") (pinfunction "8_8") (pintype "passive+no_connect"))
    )
    (net (code "65") (name "unconnected-(J3-Pad9)") (class "Default")
      (node (ref "J3") (pin "9") (pinfunction "9_9") (pintype "passive+no_connect"))
    )
    (net (code "66") (name "unconnected-(J3-PadMH1)") (class "Default")
      (node (ref "J3") (pin "MH1") (pinfunction "MH1_MH1") (pintype "passive+no_connect"))
    )
    (net (code "67") (name "unconnected-(J3-PadMH2)") (class "Default")
      (node (ref "J3") (pin "MH2") (pinfunction "MH2_MH2") (pintype "passive+no_connect"))
    )
    (net (code "68") (name "unconnected-(U1A-PA0-Pad14)") (class "Default")
      (node (ref "U1") (pin "14") (pinfunction "PA0_14") (pintype "passive+no_connect"))
    )
    (net (code "69") (name "unconnected-(U1A-PA1-Pad15)") (class "Default")
      (node (ref "U1") (pin "15") (pinfunction "PA1_15") (pintype "passive+no_connect"))
    )
    (net (code "70") (name "unconnected-(U1A-PA2-Pad16)") (class "Default")
      (node (ref "U1") (pin "16") (pinfunction "PA2_16") (pintype "passive+no_connect"))
    )
    (net (code "71") (name "unconnected-(U1A-PA3-Pad17)") (class "Default")
      (node (ref "U1") (pin "17") (pinfunction "PA3_17") (pintype "passive+no_connect"))
    )
    (net (code "72") (name "unconnected-(U1A-PA4-Pad20)") (class "Default")
      (node (ref "U1") (pin "20") (pinfunction "PA4_20") (pintype "passive+no_connect"))
    )
    (net (code "73") (name "unconnected-(U1A-PA5-Pad21)") (class "Default")
      (node (ref "U1") (pin "21") (pinfunction "PA5_21") (pintype "passive+no_connect"))
    )
    (net (code "74") (name "unconnected-(U1A-PA6-Pad22)") (class "Default")
      (node (ref "U1") (pin "22") (pinfunction "PA6_22") (pintype "passive+no_connect"))
    )
    (net (code "75") (name "unconnected-(U1A-PA7-Pad23)") (class "Default")
      (node (ref "U1") (pin "23") (pinfunction "PA7_23") (pintype "passive+no_connect"))
    )
    (net (code "76") (name "unconnected-(U1A-PA8-Pad41)") (class "Default")
      (node (ref "U1") (pin "41") (pinfunction "PA8_41") (pintype "passive+no_connect"))
    )
    (net (code "77") (name "unconnected-(U1A-PA11-Pad44)") (class "Default")
      (node (ref "U1") (pin "44") (pinfunction "PA11_44") (pintype "passive+no_connect"))
    )
    (net (code "78") (name "unconnected-(U1A-PA12-Pad45)") (class "Default")
      (node (ref "U1") (pin "45") (pinfunction "PA12_45") (pintype "passive+no_connect"))
    )
    (net (code "79") (name "unconnected-(U1A-PA15-Pad50)") (class "Default")
      (node (ref "U1") (pin "50") (pinfunction "PA15_50") (pintype "passive+no_connect"))
    )
    (net (code "80") (name "unconnected-(U1B-PB0-Pad26)") (class "Default")
      (node (ref "U1") (pin "26") (pinfunction "PB0_26") (pintype "passive"))
    )
    (net (code "81") (name "unconnected-(U1B-PB1-Pad27)") (class "Default")
      (node (ref "U1") (pin "27") (pinfunction "PB1_27") (pintype "passive"))
    )
    (net (code "82") (name "unconnected-(U1B-PB2-Pad28)") (class "Default")
      (node (ref "U1") (pin "28") (pinfunction "PB2_28") (pintype "passive"))
    )
    (net (code "83") (name "unconnected-(U1B-PB5-Pad57)") (class "Default")
      (node (ref "U1") (pin "57") (pinfunction "PB5_57") (pintype "passive"))
    )
    (net (code "84") (name "unconnected-(U1B-PB6-Pad58)") (class "Default")
      (node (ref "U1") (pin "58") (pinfunction "PB6_58") (pintype "passive"))
    )
    (net (code "85") (name "unconnected-(U1B-PB7-Pad59)") (class "Default")
      (node (ref "U1") (pin "59") (pinfunction "PB7_59") (pintype "passive"))
    )
    (net (code "86") (name "unconnected-(U1B-PB8-Pad61)") (class "Default")
      (node (ref "U1") (pin "61") (pinfunction "PB8_61") (pintype "passive"))
    )
    (net (code "87") (name "unconnected-(U1B-PB10-Pad29)") (class "Default")
      (node (ref "U1") (pin "29") (pinfunction "PB10_29") (pintype "passive"))
    )
    (net (code "88") (name "unconnected-(U1B-PB12-Pad33)") (class "Default")
      (node (ref "U1") (pin "33") (pinfunction "PB12_33") (pintype "passive"))
    )
    (net (code "89") (name "unconnected-(U1B-PB13-Pad34)") (class "Default")
      (node (ref "U1") (pin "34") (pinfunction "PB13_34") (pintype "passive"))
    )
    (net (code "90") (name "unconnected-(U1B-PB14-Pad35)") (class "Default")
      (node (ref "U1") (pin "35") (pinfunction "PB14_35") (pintype "passive"))
    )
    (net (code "91") (name "unconnected-(U1B-PB15-Pad36)") (class "Default")
      (node (ref "U1") (pin "36") (pinfunction "PB15_36") (pintype "passive"))
    )
    (net (code "92") (name "unconnected-(U1B-PD2-Pad54)") (class "Default")
      (node (ref "U1") (pin "54") (pinfunction "PD2_54") (pintype "passive"))
    )
    (net (code "93") (name "unconnected-(VT1-D-Pad3)") (class "Default")
      (node (ref "VT1") (pin "3") (pinfunction "D_3") (pintype "passive"))
    )
    (net (code "94") (name "unconnected-(VT1-S-Pad2)") (class "Default")
      (node (ref "VT1") (pin "2") (pinfunction "S_2") (pintype "passive"))
    )
  )
)
